# Gate_Drive.net
KiCad netlist of a schematic drawn in Altium Designer
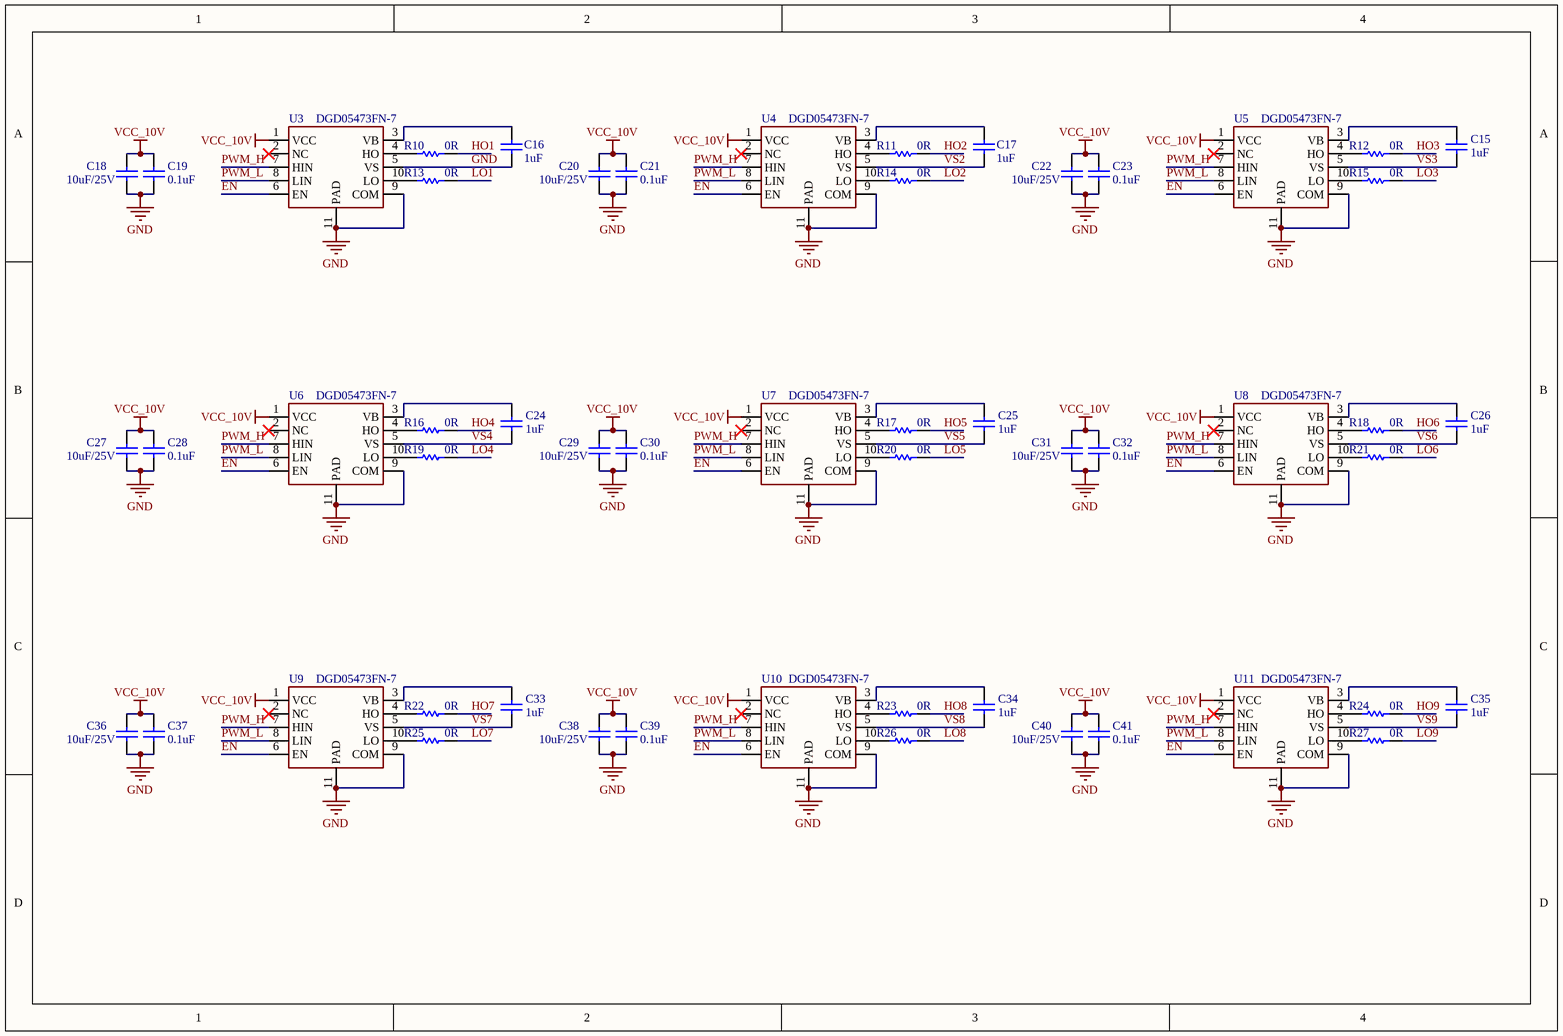
[diagram p0: Gate_Drive.SchDoc]

(export (version "E")
  (design (tool "Eeschema 10.0.6"))
  (components
    (comp (ref "C15")
      (value "1uF")
      (footprint "C0603_M")
      (description "Capacitor")
      (fields (field (name "PUBLISHER") "Altium Limited"))
      (libsource (lib "Miscellaneous Devices") (part "Cap"))
    )
    (comp (ref "C16")
      (value "1uF")
      (footprint "C0603_M")
      (description "Capacitor")
      (fields (field (name "PUBLISHER") "Altium Limited"))
      (libsource (lib "Miscellaneous Devices") (part "Cap"))
    )
    (comp (ref "C17")
      (value "1uF")
      (footprint "C0603_M")
      (description "Capacitor")
      (fields (field (name "PUBLISHER") "Altium Limited"))
      (libsource (lib "Miscellaneous Devices") (part "Cap"))
    )
    (comp (ref "C18")
      (value "10uF/25V")
      (footprint "C0603_M")
      (description "Capacitor")
      (fields (field (name "PUBLISHER") "Altium Limited"))
      (libsource (lib "Miscellaneous Devices") (part "Cap"))
    )
    (comp (ref "C19")
      (value "0.1uF")
      (footprint "C0603_M")
      (description "Capacitor")
      (fields (field (name "PUBLISHER") "Altium Limited"))
      (libsource (lib "Miscellaneous Devices") (part "Cap"))
    )
    (comp (ref "C20")
      (value "10uF/25V")
      (footprint "C0603_M")
      (description "Capacitor")
      (fields (field (name "PUBLISHER") "Altium Limited"))
      (libsource (lib "Miscellaneous Devices") (part "Cap"))
    )
    (comp (ref "C21")
      (value "0.1uF")
      (footprint "C0603_M")
      (description "Capacitor")
      (fields (field (name "PUBLISHER") "Altium Limited"))
      (libsource (lib "Miscellaneous Devices") (part "Cap"))
    )
    (comp (ref "C22")
      (value "10uF/25V")
      (footprint "C0603_M")
      (description "Capacitor")
      (fields (field (name "PUBLISHER") "Altium Limited"))
      (libsource (lib "Miscellaneous Devices") (part "Cap"))
    )
    (comp (ref "C23")
      (value "0.1uF")
      (footprint "C0603_M")
      (description "Capacitor")
      (fields (field (name "PUBLISHER") "Altium Limited"))
      (libsource (lib "Miscellaneous Devices") (part "Cap"))
    )
    (comp (ref "C24")
      (value "1uF")
      (footprint "C0603_M")
      (description "Capacitor")
      (fields (field (name "PUBLISHER") "Altium Limited"))
      (libsource (lib "Miscellaneous Devices") (part "Cap"))
    )
    (comp (ref "C25")
      (value "1uF")
      (footprint "C0603_M")
      (description "Capacitor")
      (fields (field (name "PUBLISHER") "Altium Limited"))
      (libsource (lib "Miscellaneous Devices") (part "Cap"))
    )
    (comp (ref "C26")
      (value "1uF")
      (footprint "C0603_M")
      (description "Capacitor")
      (fields (field (name "PUBLISHER") "Altium Limited"))
      (libsource (lib "Miscellaneous Devices") (part "Cap"))
    )
    (comp (ref "C27")
      (value "10uF/25V")
      (footprint "C0603_M")
      (description "Capacitor")
      (fields (field (name "PUBLISHER") "Altium Limited"))
      (libsource (lib "Miscellaneous Devices") (part "Cap"))
    )
    (comp (ref "C28")
      (value "0.1uF")
      (footprint "C0603_M")
      (description "Capacitor")
      (fields (field (name "PUBLISHER") "Altium Limited"))
      (libsource (lib "Miscellaneous Devices") (part "Cap"))
    )
    (comp (ref "C29")
      (value "10uF/25V")
      (footprint "C0603_M")
      (description "Capacitor")
      (fields (field (name "PUBLISHER") "Altium Limited"))
      (libsource (lib "Miscellaneous Devices") (part "Cap"))
    )
    (comp (ref "C30")
      (value "0.1uF")
      (footprint "C0603_M")
      (description "Capacitor")
      (fields (field (name "PUBLISHER") "Altium Limited"))
      (libsource (lib "Miscellaneous Devices") (part "Cap"))
    )
    (comp (ref "C31")
      (value "10uF/25V")
      (footprint "C0603_M")
      (description "Capacitor")
      (fields (field (name "PUBLISHER") "Altium Limited"))
      (libsource (lib "Miscellaneous Devices") (part "Cap"))
    )
    (comp (ref "C32")
      (value "0.1uF")
      (footprint "C0603_M")
      (description "Capacitor")
      (fields (field (name "PUBLISHER") "Altium Limited"))
      (libsource (lib "Miscellaneous Devices") (part "Cap"))
    )
    (comp (ref "C33")
      (value "1uF")
      (footprint "C0603_M")
      (description "Capacitor")
      (fields (field (name "PUBLISHER") "Altium Limited"))
      (libsource (lib "Miscellaneous Devices") (part "Cap"))
    )
    (comp (ref "C34")
      (value "1uF")
      (footprint "C0603_M")
      (description "Capacitor")
      (fields (field (name "PUBLISHER") "Altium Limited"))
      (libsource (lib "Miscellaneous Devices") (part "Cap"))
    )
    (comp (ref "C35")
      (value "1uF")
      (footprint "C0603_M")
      (description "Capacitor")
      (fields (field (name "PUBLISHER") "Altium Limited"))
      (libsource (lib "Miscellaneous Devices") (part "Cap"))
    )
    (comp (ref "C36")
      (value "10uF/25V")
      (footprint "C0603_M")
      (description "Capacitor")
      (fields (field (name "PUBLISHER") "Altium Limited"))
      (libsource (lib "Miscellaneous Devices") (part "Cap"))
    )
    (comp (ref "C37")
      (value "0.1uF")
      (footprint "C0603_M")
      (description "Capacitor")
      (fields (field (name "PUBLISHER") "Altium Limited"))
      (libsource (lib "Miscellaneous Devices") (part "Cap"))
    )
    (comp (ref "C38")
      (value "10uF/25V")
      (footprint "C0603_M")
      (description "Capacitor")
      (fields (field (name "PUBLISHER") "Altium Limited"))
      (libsource (lib "Miscellaneous Devices") (part "Cap"))
    )
    (comp (ref "C39")
      (value "0.1uF")
      (footprint "C0603_M")
      (description "Capacitor")
      (fields (field (name "PUBLISHER") "Altium Limited"))
      (libsource (lib "Miscellaneous Devices") (part "Cap"))
    )
    (comp (ref "C40")
      (value "10uF/25V")
      (footprint "C0603_M")
      (description "Capacitor")
      (fields (field (name "PUBLISHER") "Altium Limited"))
      (libsource (lib "Miscellaneous Devices") (part "Cap"))
    )
    (comp (ref "C41")
      (value "0.1uF")
      (footprint "C0603_M")
      (description "Capacitor")
      (fields (field (name "PUBLISHER") "Altium Limited"))
      (libsource (lib "Miscellaneous Devices") (part "Cap"))
    )
    (comp (ref "R10")
      (value "0R")
      (footprint "R0603_M")
      (description "Resistor")
      (libsource (lib "Miscellaneous Devices") (part "Res1"))
    )
    (comp (ref "R11")
      (value "0R")
      (footprint "R0603_M")
      (description "Resistor")
      (libsource (lib "Miscellaneous Devices") (part "Res1"))
    )
    (comp (ref "R12")
      (value "0R")
      (footprint "R0603_M")
      (description "Resistor")
      (libsource (lib "Miscellaneous Devices") (part "Res1"))
    )
    (comp (ref "R13")
      (value "0R")
      (footprint "R0603_M")
      (description "Resistor")
      (libsource (lib "Miscellaneous Devices") (part "Res1"))
    )
    (comp (ref "R14")
      (value "0R")
      (footprint "R0603_M")
      (description "Resistor")
      (libsource (lib "Miscellaneous Devices") (part "Res1"))
    )
    (comp (ref "R15")
      (value "0R")
      (footprint "R0603_M")
      (description "Resistor")
      (libsource (lib "Miscellaneous Devices") (part "Res1"))
    )
    (comp (ref "R16")
      (value "0R")
      (footprint "R0603_M")
      (description "Resistor")
      (libsource (lib "Miscellaneous Devices") (part "Res1"))
    )
    (comp (ref "R17")
      (value "0R")
      (footprint "R0603_M")
      (description "Resistor")
      (libsource (lib "Miscellaneous Devices") (part "Res1"))
    )
    (comp (ref "R18")
      (value "0R")
      (footprint "R0603_M")
      (description "Resistor")
      (libsource (lib "Miscellaneous Devices") (part "Res1"))
    )
    (comp (ref "R19")
      (value "0R")
      (footprint "R0603_M")
      (description "Resistor")
      (libsource (lib "Miscellaneous Devices") (part "Res1"))
    )
    (comp (ref "R20")
      (value "0R")
      (footprint "R0603_M")
      (description "Resistor")
      (libsource (lib "Miscellaneous Devices") (part "Res1"))
    )
    (comp (ref "R21")
      (value "0R")
      (footprint "R0603_M")
      (description "Resistor")
      (libsource (lib "Miscellaneous Devices") (part "Res1"))
    )
    (comp (ref "R22")
      (value "0R")
      (footprint "R0603_M")
      (description "Resistor")
      (libsource (lib "Miscellaneous Devices") (part "Res1"))
    )
    (comp (ref "R23")
      (value "0R")
      (footprint "R0603_M")
      (description "Resistor")
      (libsource (lib "Miscellaneous Devices") (part "Res1"))
    )
    (comp (ref "R24")
      (value "0R")
      (footprint "R0603_M")
      (description "Resistor")
      (libsource (lib "Miscellaneous Devices") (part "Res1"))
    )
    (comp (ref "R25")
      (value "0R")
      (footprint "R0603_M")
      (description "Resistor")
      (libsource (lib "Miscellaneous Devices") (part "Res1"))
    )
    (comp (ref "R26")
      (value "0R")
      (footprint "R0603_M")
      (description "Resistor")
      (libsource (lib "Miscellaneous Devices") (part "Res1"))
    )
    (comp (ref "R27")
      (value "0R")
      (footprint "R0603_M")
      (description "Resistor")
      (libsource (lib "Miscellaneous Devices") (part "Res1"))
    )
    (comp (ref "U3")
      (value "DGD05473FN-7")
      (footprint "W-DFN3030-10_L3.0-W3.0-P0.50-BL-EP")
      (libsource (lib "my_library") (part "DGD05473"))
    )
    (comp (ref "U4")
      (value "DGD05473FN-7")
      (footprint "W-DFN3030-10_L3.0-W3.0-P0.50-BL-EP")
      (libsource (lib "my_library") (part "DGD05473"))
    )
    (comp (ref "U5")
      (value "DGD05473FN-7")
      (footprint "W-DFN3030-10_L3.0-W3.0-P0.50-BL-EP")
      (libsource (lib "my_library") (part "DGD05473"))
    )
    (comp (ref "U6")
      (value "DGD05473FN-7")
      (footprint "W-DFN3030-10_L3.0-W3.0-P0.50-BL-EP")
      (libsource (lib "my_library") (part "DGD05473"))
    )
    (comp (ref "U7")
      (value "DGD05473FN-7")
      (footprint "W-DFN3030-10_L3.0-W3.0-P0.50-BL-EP")
      (libsource (lib "my_library") (part "DGD05473"))
    )
    (comp (ref "U8")
      (value "DGD05473FN-7")
      (footprint "W-DFN3030-10_L3.0-W3.0-P0.50-BL-EP")
      (libsource (lib "my_library") (part "DGD05473"))
    )
    (comp (ref "U9")
      (value "DGD05473FN-7")
      (footprint "W-DFN3030-10_L3.0-W3.0-P0.50-BL-EP")
      (libsource (lib "my_library") (part "DGD05473"))
    )
    (comp (ref "U10")
      (value "DGD05473FN-7")
      (footprint "W-DFN3030-10_L3.0-W3.0-P0.50-BL-EP")
      (libsource (lib "my_library") (part "DGD05473"))
    )
    (comp (ref "U11")
      (value "DGD05473FN-7")
      (footprint "W-DFN3030-10_L3.0-W3.0-P0.50-BL-EP")
      (libsource (lib "my_library") (part "DGD05473"))
    )
  )
  (nets
    (net (code "1") (name "/EN") (class "Default")
      (node (ref "U10") (pin "6") (pinfunction "EN_6") (pintype "passive"))
      (node (ref "U11") (pin "6") (pinfunction "EN_6") (pintype "passive"))
      (node (ref "U3") (pin "6") (pinfunction "EN_6") (pintype "passive"))
      (node (ref "U4") (pin "6") (pinfunction "EN_6") (pintype "passive"))
      (node (ref "U5") (pin "6") (pinfunction "EN_6") (pintype "passive"))
      (node (ref "U6") (pin "6") (pinfunction "EN_6") (pintype "passive"))
      (node (ref "U7") (pin "6") (pinfunction "EN_6") (pintype "passive"))
      (node (ref "U8") (pin "6") (pinfunction "EN_6") (pintype "passive"))
      (node (ref "U9") (pin "6") (pinfunction "EN_6") (pintype "passive"))
    )
    (net (code "2") (name "/HO1") (class "Default")
      (node (ref "R10") (pin "2") (pinfunction "2_2") (pintype "passive"))
    )
    (net (code "3") (name "/HO2") (class "Default")
      (node (ref "R11") (pin "2") (pinfunction "2_2") (pintype "passive"))
    )
    (net (code "4") (name "/HO3") (class "Default")
      (node (ref "R12") (pin "2") (pinfunction "2_2") (pintype "passive"))
    )
    (net (code "5") (name "/HO4") (class "Default")
      (node (ref "R16") (pin "2") (pinfunction "2_2") (pintype "passive"))
    )
    (net (code "6") (name "/HO5") (class "Default")
      (node (ref "R17") (pin "2") (pinfunction "2_2") (pintype "passive"))
    )
    (net (code "7") (name "/HO6") (class "Default")
      (node (ref "R18") (pin "2") (pinfunction "2_2") (pintype "passive"))
    )
    (net (code "8") (name "/HO7") (class "Default")
      (node (ref "R22") (pin "2") (pinfunction "2_2") (pintype "passive"))
    )
    (net (code "9") (name "/HO8") (class "Default")
      (node (ref "R23") (pin "2") (pinfunction "2_2") (pintype "passive"))
    )
    (net (code "10") (name "/HO9") (class "Default")
      (node (ref "R24") (pin "2") (pinfunction "2_2") (pintype "passive"))
    )
    (net (code "11") (name "/LO1") (class "Default")
      (node (ref "R13") (pin "2") (pinfunction "2_2") (pintype "passive"))
    )
    (net (code "12") (name "/LO2") (class "Default")
      (node (ref "R14") (pin "2") (pinfunction "2_2") (pintype "passive"))
    )
    (net (code "13") (name "/LO3") (class "Default")
      (node (ref "R15") (pin "2") (pinfunction "2_2") (pintype "passive"))
    )
    (net (code "14") (name "/LO4") (class "Default")
      (node (ref "R19") (pin "2") (pinfunction "2_2") (pintype "passive"))
    )
    (net (code "15") (name "/LO5") (class "Default")
      (node (ref "R20") (pin "2") (pinfunction "2_2") (pintype "passive"))
    )
    (net (code "16") (name "/LO6") (class "Default")
      (node (ref "R21") (pin "2") (pinfunction "2_2") (pintype "passive"))
    )
    (net (code "17") (name "/LO7") (class "Default")
      (node (ref "R25") (pin "2") (pinfunction "2_2") (pintype "passive"))
    )
    (net (code "18") (name "/LO8") (class "Default")
      (node (ref "R26") (pin "2") (pinfunction "2_2") (pintype "passive"))
    )
    (net (code "19") (name "/LO9") (class "Default")
      (node (ref "R27") (pin "2") (pinfunction "2_2") (pintype "passive"))
    )
    (net (code "20") (name "/PWM_H") (class "Default")
      (node (ref "U10") (pin "7") (pinfunction "HIN_7") (pintype "passive"))
      (node (ref "U11") (pin "7") (pinfunction "HIN_7") (pintype "passive"))
      (node (ref "U3") (pin "7") (pinfunction "HIN_7") (pintype "passive"))
      (node (ref "U4") (pin "7") (pinfunction "HIN_7") (pintype "passive"))
      (node (ref "U5") (pin "7") (pinfunction "HIN_7") (pintype "passive"))
      (node (ref "U6") (pin "7") (pinfunction "HIN_7") (pintype "passive"))
      (node (ref "U7") (pin "7") (pinfunction "HIN_7") (pintype "passive"))
      (node (ref "U8") (pin "7") (pinfunction "HIN_7") (pintype "passive"))
      (node (ref "U9") (pin "7") (pinfunction "HIN_7") (pintype "passive"))
    )
    (net (code "21") (name "/PWM_L") (class "Default")
      (node (ref "U10") (pin "8") (pinfunction "LIN_8") (pintype "passive"))
      (node (ref "U11") (pin "8") (pinfunction "LIN_8") (pintype "passive"))
      (node (ref "U3") (pin "8") (pinfunction "LIN_8") (pintype "passive"))
      (node (ref "U4") (pin "8") (pinfunction "LIN_8") (pintype "passive"))
      (node (ref "U5") (pin "8") (pinfunction "LIN_8") (pintype "passive"))
      (node (ref "U6") (pin "8") (pinfunction "LIN_8") (pintype "passive"))
      (node (ref "U7") (pin "8") (pinfunction "LIN_8") (pintype "passive"))
      (node (ref "U8") (pin "8") (pinfunction "LIN_8") (pintype "passive"))
      (node (ref "U9") (pin "8") (pinfunction "LIN_8") (pintype "passive"))
    )
    (net (code "22") (name "/VS2") (class "Default")
      (node (ref "C17") (pin "1") (pinfunction "1_1") (pintype "passive"))
      (node (ref "U4") (pin "5") (pinfunction "VS_5") (pintype "passive"))
    )
    (net (code "23") (name "/VS3") (class "Default")
      (node (ref "C15") (pin "1") (pinfunction "1_1") (pintype "passive"))
      (node (ref "U5") (pin "5") (pinfunction "VS_5") (pintype "passive"))
    )
    (net (code "24") (name "/VS4") (class "Default")
      (node (ref "C24") (pin "1") (pinfunction "1_1") (pintype "passive"))
      (node (ref "U6") (pin "5") (pinfunction "VS_5") (pintype "passive"))
    )
    (net (code "25") (name "/VS5") (class "Default")
      (node (ref "C25") (pin "1") (pinfunction "1_1") (pintype "passive"))
      (node (ref "U7") (pin "5") (pinfunction "VS_5") (pintype "passive"))
    )
    (net (code "26") (name "/VS6") (class "Default")
      (node (ref "C26") (pin "1") (pinfunction "1_1") (pintype "passive"))
      (node (ref "U8") (pin "5") (pinfunction "VS_5") (pintype "passive"))
    )
    (net (code "27") (name "/VS7") (class "Default")
      (node (ref "C33") (pin "1") (pinfunction "1_1") (pintype "passive"))
      (node (ref "U9") (pin "5") (pinfunction "VS_5") (pintype "passive"))
    )
    (net (code "28") (name "/VS8") (class "Default")
      (node (ref "C34") (pin "1") (pinfunction "1_1") (pintype "passive"))
      (node (ref "U10") (pin "5") (pinfunction "VS_5") (pintype "passive"))
    )
    (net (code "29") (name "/VS9") (class "Default")
      (node (ref "C35") (pin "1") (pinfunction "1_1") (pintype "passive"))
      (node (ref "U11") (pin "5") (pinfunction "VS_5") (pintype "passive"))
    )
    (net (code "30") (name "GND") (class "Default")
      (node (ref "C16") (pin "1") (pinfunction "1_1") (pintype "passive"))
      (node (ref "C18") (pin "2") (pinfunction "2_2") (pintype "passive"))
      (node (ref "C19") (pin "2") (pinfunction "2_2") (pintype "passive"))
      (node (ref "C20") (pin "2") (pinfunction "2_2") (pintype "passive"))
      (node (ref "C21") (pin "2") (pinfunction "2_2") (pintype "passive"))
      (node (ref "C22") (pin "2") (pinfunction "2_2") (pintype "passive"))
      (node (ref "C23") (pin "2") (pinfunction "2_2") (pintype "passive"))
      (node (ref "C27") (pin "2") (pinfunction "2_2") (pintype "passive"))
      (node (ref "C28") (pin "2") (pinfunction "2_2") (pintype "passive"))
      (node (ref "C29") (pin "2") (pinfunction "2_2") (pintype "passive"))
      (node (ref "C30") (pin "2") (pinfunction "2_2") (pintype "passive"))
      (node (ref "C31") (pin "2") (pinfunction "2_2") (pintype "passive"))
      (node (ref "C32") (pin "2") (pinfunction "2_2") (pintype "passive"))
      (node (ref "C36") (pin "2") (pinfunction "2_2") (pintype "passive"))
      (node (ref "C37") (pin "2") (pinfunction "2_2") (pintype "passive"))
      (node (ref "C38") (pin "2") (pinfunction "2_2") (pintype "passive"))
      (node (ref "C39") (pin "2") (pinfunction "2_2") (pintype "passive"))
      (node (ref "C40") (pin "2") (pinfunction "2_2") (pintype "passive"))
      (node (ref "C41") (pin "2") (pinfunction "2_2") (pintype "passive"))
      (node (ref "U10") (pin "11") (pinfunction "PAD_11") (pintype "passive"))
      (node (ref "U10") (pin "9") (pinfunction "COM_9") (pintype "passive"))
      (node (ref "U11") (pin "11") (pinfunction "PAD_11") (pintype "passive"))
      (node (ref "U11") (pin "9") (pinfunction "COM_9") (pintype "passive"))
      (node (ref "U3") (pin "11") (pinfunction "PAD_11") (pintype "passive"))
      (node (ref "U3") (pin "5") (pinfunction "VS_5") (pintype "passive"))
      (node (ref "U3") (pin "9") (pinfunction "COM_9") (pintype "passive"))
      (node (ref "U4") (pin "11") (pinfunction "PAD_11") (pintype "passive"))
      (node (ref "U4") (pin "9") (pinfunction "COM_9") (pintype "passive"))
      (node (ref "U5") (pin "11") (pinfunction "PAD_11") (pintype "passive"))
      (node (ref "U5") (pin "9") (pinfunction "COM_9") (pintype "passive"))
      (node (ref "U6") (pin "11") (pinfunction "PAD_11") (pintype "passive"))
      (node (ref "U6") (pin "9") (pinfunction "COM_9") (pintype "passive"))
      (node (ref "U7") (pin "11") (pinfunction "PAD_11") (pintype "passive"))
      (node (ref "U7") (pin "9") (pinfunction "COM_9") (pintype "passive"))
      (node (ref "U8") (pin "11") (pinfunction "PAD_11") (pintype "passive"))
      (node (ref "U8") (pin "9") (pinfunction "COM_9") (pintype "passive"))
      (node (ref "U9") (pin "11") (pinfunction "PAD_11") (pintype "passive"))
      (node (ref "U9") (pin "9") (pinfunction "COM_9") (pintype "passive"))
    )
    (net (code "31") (name "Net-(U3-HO)") (class "Default")
      (node (ref "R10") (pin "1") (pinfunction "1_1") (pintype "passive"))
      (node (ref "U3") (pin "4") (pinfunction "HO_4") (pintype "passive"))
    )
    (net (code "32") (name "Net-(U3-LO)") (class "Default")
      (node (ref "R13") (pin "1") (pinfunction "1_1") (pintype "passive"))
      (node (ref "U3") (pin "10") (pinfunction "LO_10") (pintype "passive"))
    )
    (net (code "33") (name "Net-(U3-VB)") (class "Default")
      (node (ref "C16") (pin "2") (pinfunction "2_2") (pintype "passive"))
      (node (ref "U3") (pin "3") (pinfunction "VB_3") (pintype "passive"))
    )
    (net (code "34") (name "Net-(U4-HO)") (class "Default")
      (node (ref "R11") (pin "1") (pinfunction "1_1") (pintype "passive"))
      (node (ref "U4") (pin "4") (pinfunction "HO_4") (pintype "passive"))
    )
    (net (code "35") (name "Net-(U4-LO)") (class "Default")
      (node (ref "R14") (pin "1") (pinfunction "1_1") (pintype "passive"))
      (node (ref "U4") (pin "10") (pinfunction "LO_10") (pintype "passive"))
    )
    (net (code "36") (name "Net-(U4-VB)") (class "Default")
      (node (ref "C17") (pin "2") (pinfunction "2_2") (pintype "passive"))
      (node (ref "U4") (pin "3") (pinfunction "VB_3") (pintype "passive"))
    )
    (net (code "37") (name "Net-(U5-HO)") (class "Default")
      (node (ref "R12") (pin "1") (pinfunction "1_1") (pintype "passive"))
      (node (ref "U5") (pin "4") (pinfunction "HO_4") (pintype "passive"))
    )
    (net (code "38") (name "Net-(U5-LO)") (class "Default")
      (node (ref "R15") (pin "1") (pinfunction "1_1") (pintype "passive"))
      (node (ref "U5") (pin "10") (pinfunction "LO_10") (pintype "passive"))
    )
    (net (code "39") (name "Net-(U5-VB)") (class "Default")
      (node (ref "C15") (pin "2") (pinfunction "2_2") (pintype "passive"))
      (node (ref "U5") (pin "3") (pinfunction "VB_3") (pintype "passive"))
    )
    (net (code "40") (name "Net-(U6-HO)") (class "Default")
      (node (ref "R16") (pin "1") (pinfunction "1_1") (pintype "passive"))
      (node (ref "U6") (pin "4") (pinfunction "HO_4") (pintype "passive"))
    )
    (net (code "41") (name "Net-(U6-LO)") (class "Default")
      (node (ref "R19") (pin "1") (pinfunction "1_1") (pintype "passive"))
      (node (ref "U6") (pin "10") (pinfunction "LO_10") (pintype "passive"))
    )
    (net (code "42") (name "Net-(U6-VB)") (class "Default")
      (node (ref "C24") (pin "2") (pinfunction "2_2") (pintype "passive"))
      (node (ref "U6") (pin "3") (pinfunction "VB_3") (pintype "passive"))
    )
    (net (code "43") (name "Net-(U7-HO)") (class "Default")
      (node (ref "R17") (pin "1") (pinfunction "1_1") (pintype "passive"))
      (node (ref "U7") (pin "4") (pinfunction "HO_4") (pintype "passive"))
    )
    (net (code "44") (name "Net-(U7-LO)") (class "Default")
      (node (ref "R20") (pin "1") (pinfunction "1_1") (pintype "passive"))
      (node (ref "U7") (pin "10") (pinfunction "LO_10") (pintype "passive"))
    )
    (net (code "45") (name "Net-(U7-VB)") (class "Default")
      (node (ref "C25") (pin "2") (pinfunction "2_2") (pintype "passive"))
      (node (ref "U7") (pin "3") (pinfunction "VB_3") (pintype "passive"))
    )
    (net (code "46") (name "Net-(U8-HO)") (class "Default")
      (node (ref "R18") (pin "1") (pinfunction "1_1") (pintype "passive"))
      (node (ref "U8") (pin "4") (pinfunction "HO_4") (pintype "passive"))
    )
    (net (code "47") (name "Net-(U8-LO)") (class "Default")
      (node (ref "R21") (pin "1") (pinfunction "1_1") (pintype "passive"))
      (node (ref "U8") (pin "10") (pinfunction "LO_10") (pintype "passive"))
    )
    (net (code "48") (name "Net-(U8-VB)") (class "Default")
      (node (ref "C26") (pin "2") (pinfunction "2_2") (pintype "passive"))
      (node (ref "U8") (pin "3") (pinfunction "VB_3") (pintype "passive"))
    )
    (net (code "49") (name "Net-(U9-HO)") (class "Default")
      (node (ref "R22") (pin "1") (pinfunction "1_1") (pintype "passive"))
      (node (ref "U9") (pin "4") (pinfunction "HO_4") (pintype "passive"))
    )
    (net (code "50") (name "Net-(U9-LO)") (class "Default")
      (node (ref "R25") (pin "1") (pinfunction "1_1") (pintype "passive"))
      (node (ref "U9") (pin "10") (pinfunction "LO_10") (pintype "passive"))
    )
    (net (code "51") (name "Net-(U9-VB)") (class "Default")
      (node (ref "C33") (pin "2") (pinfunction "2_2") (pintype "passive"))
      (node (ref "U9") (pin "3") (pinfunction "VB_3") (pintype "passive"))
    )
    (net (code "52") (name "Net-(U10-HO)") (class "Default")
      (node (ref "R23") (pin "1") (pinfunction "1_1") (pintype "passive"))
      (node (ref "U10") (pin "4") (pinfunction "HO_4") (pintype "passive"))
    )
    (net (code "53") (name "Net-(U10-LO)") (class "Default")
      (node (ref "R26") (pin "1") (pinfunction "1_1") (pintype "passive"))
      (node (ref "U10") (pin "10") (pinfunction "LO_10") (pintype "passive"))
    )
    (net (code "54") (name "Net-(U10-VB)") (class "Default")
      (node (ref "C34") (pin "2") (pinfunction "2_2") (pintype "passive"))
      (node (ref "U10") (pin "3") (pinfunction "VB_3") (pintype "passive"))
    )
    (net (code "55") (name "Net-(U11-HO)") (class "Default")
      (node (ref "R24") (pin "1") (pinfunction "1_1") (pintype "passive"))
      (node (ref "U11") (pin "4") (pinfunction "HO_4") (pintype "passive"))
    )
    (net (code "56") (name "Net-(U11-LO)") (class "Default")
      (node (ref "R27") (pin "1") (pinfunction "1_1") (pintype "passive"))
      (node (ref "U11") (pin "10") (pinfunction "LO_10") (pintype "passive"))
    )
    (net (code "57") (name "Net-(U11-VB)") (class "Default")
      (node (ref "C35") (pin "2") (pinfunction "2_2") (pintype "passive"))
      (node (ref "U11") (pin "3") (pinfunction "VB_3") (pintype "passive"))
    )
    (net (code "58") (name "VCC_10V") (class "Default")
      (node (ref "C18") (pin "1") (pinfunction "1_1") (pintype "passive"))
      (node (ref "C19") (pin "1") (pinfunction "1_1") (pintype "passive"))
      (node (ref "C20") (pin "1") (pinfunction "1_1") (pintype "passive"))
      (node (ref "C21") (pin "1") (pinfunction "1_1") (pintype "passive"))
      (node (ref "C22") (pin "1") (pinfunction "1_1") (pintype "passive"))
      (node (ref "C23") (pin "1") (pinfunction "1_1") (pintype "passive"))
      (node (ref "C27") (pin "1") (pinfunction "1_1") (pintype "passive"))
      (node (ref "C28") (pin "1") (pinfunction "1_1") (pintype "passive"))
      (node (ref "C29") (pin "1") (pinfunction "1_1") (pintype "passive"))
      (node (ref "C30") (pin "1") (pinfunction "1_1") (pintype "passive"))
      (node (ref "C31") (pin "1") (pinfunction "1_1") (pintype "passive"))
      (node (ref "C32") (pin "1") (pinfunction "1_1") (pintype "passive"))
      (node (ref "C36") (pin "1") (pinfunction "1_1") (pintype "passive"))
      (node (ref "C37") (pin "1") (pinfunction "1_1") (pintype "passive"))
      (node (ref "C38") (pin "1") (pinfunction "1_1") (pintype "passive"))
      (node (ref "C39") (pin "1") (pinfunction "1_1") (pintype "passive"))
      (node (ref "C40") (pin "1") (pinfunction "1_1") (pintype "passive"))
      (node (ref "C41") (pin "1") (pinfunction "1_1") (pintype "passive"))
      (node (ref "U10") (pin "1") (pinfunction "VCC_1") (pintype "passive"))
      (node (ref "U11") (pin "1") (pinfunction "VCC_1") (pintype "passive"))
      (node (ref "U3") (pin "1") (pinfunction "VCC_1") (pintype "passive"))
      (node (ref "U4") (pin "1") (pinfunction "VCC_1") (pintype "passive"))
      (node (ref "U5") (pin "1") (pinfunction "VCC_1") (pintype "passive"))
      (node (ref "U6") (pin "1") (pinfunction "VCC_1") (pintype "passive"))
      (node (ref "U7") (pin "1") (pinfunction "VCC_1") (pintype "passive"))
      (node (ref "U8") (pin "1") (pinfunction "VCC_1") (pintype "passive"))
      (node (ref "U9") (pin "1") (pinfunction "VCC_1") (pintype "passive"))
    )
    (net (code "59") (name "unconnected-(U3-NC-Pad2)") (class "Default")
      (node (ref "U3") (pin "2") (pinfunction "NC_2") (pintype "passive+no_connect"))
    )
    (net (code "60") (name "unconnected-(U4-NC-Pad2)") (class "Default")
      (node (ref "U4") (pin "2") (pinfunction "NC_2") (pintype "passive+no_connect"))
    )
    (net (code "61") (name "unconnected-(U5-NC-Pad2)") (class "Default")
      (node (ref "U5") (pin "2") (pinfunction "NC_2") (pintype "passive+no_connect"))
    )
    (net (code "62") (name "unconnected-(U6-NC-Pad2)") (class "Default")
      (node (ref "U6") (pin "2") (pinfunction "NC_2") (pintype "passive+no_connect"))
    )
    (net (code "63") (name "unconnected-(U7-NC-Pad2)") (class "Default")
      (node (ref "U7") (pin "2") (pinfunction "NC_2") (pintype "passive+no_connect"))
    )
    (net (code "64") (name "unconnected-(U8-NC-Pad2)") (class "Default")
      (node (ref "U8") (pin "2") (pinfunction "NC_2") (pintype "passive+no_connect"))
    )
    (net (code "65") (name "unconnected-(U9-NC-Pad2)") (class "Default")
      (node (ref "U9") (pin "2") (pinfunction "NC_2") (pintype "passive+no_connect"))
    )
    (net (code "66") (name "unconnected-(U10-NC-Pad2)") (class "Default")
      (node (ref "U10") (pin "2") (pinfunction "NC_2") (pintype "passive+no_connect"))
    )
    (net (code "67") (name "unconnected-(U11-NC-Pad2)") (class "Default")
      (node (ref "U11") (pin "2") (pinfunction "NC_2") (pintype "passive+no_connect"))
    )
  )
)
